# LOGIC.net
KiCad netlist of a schematic drawn in Altium Designer
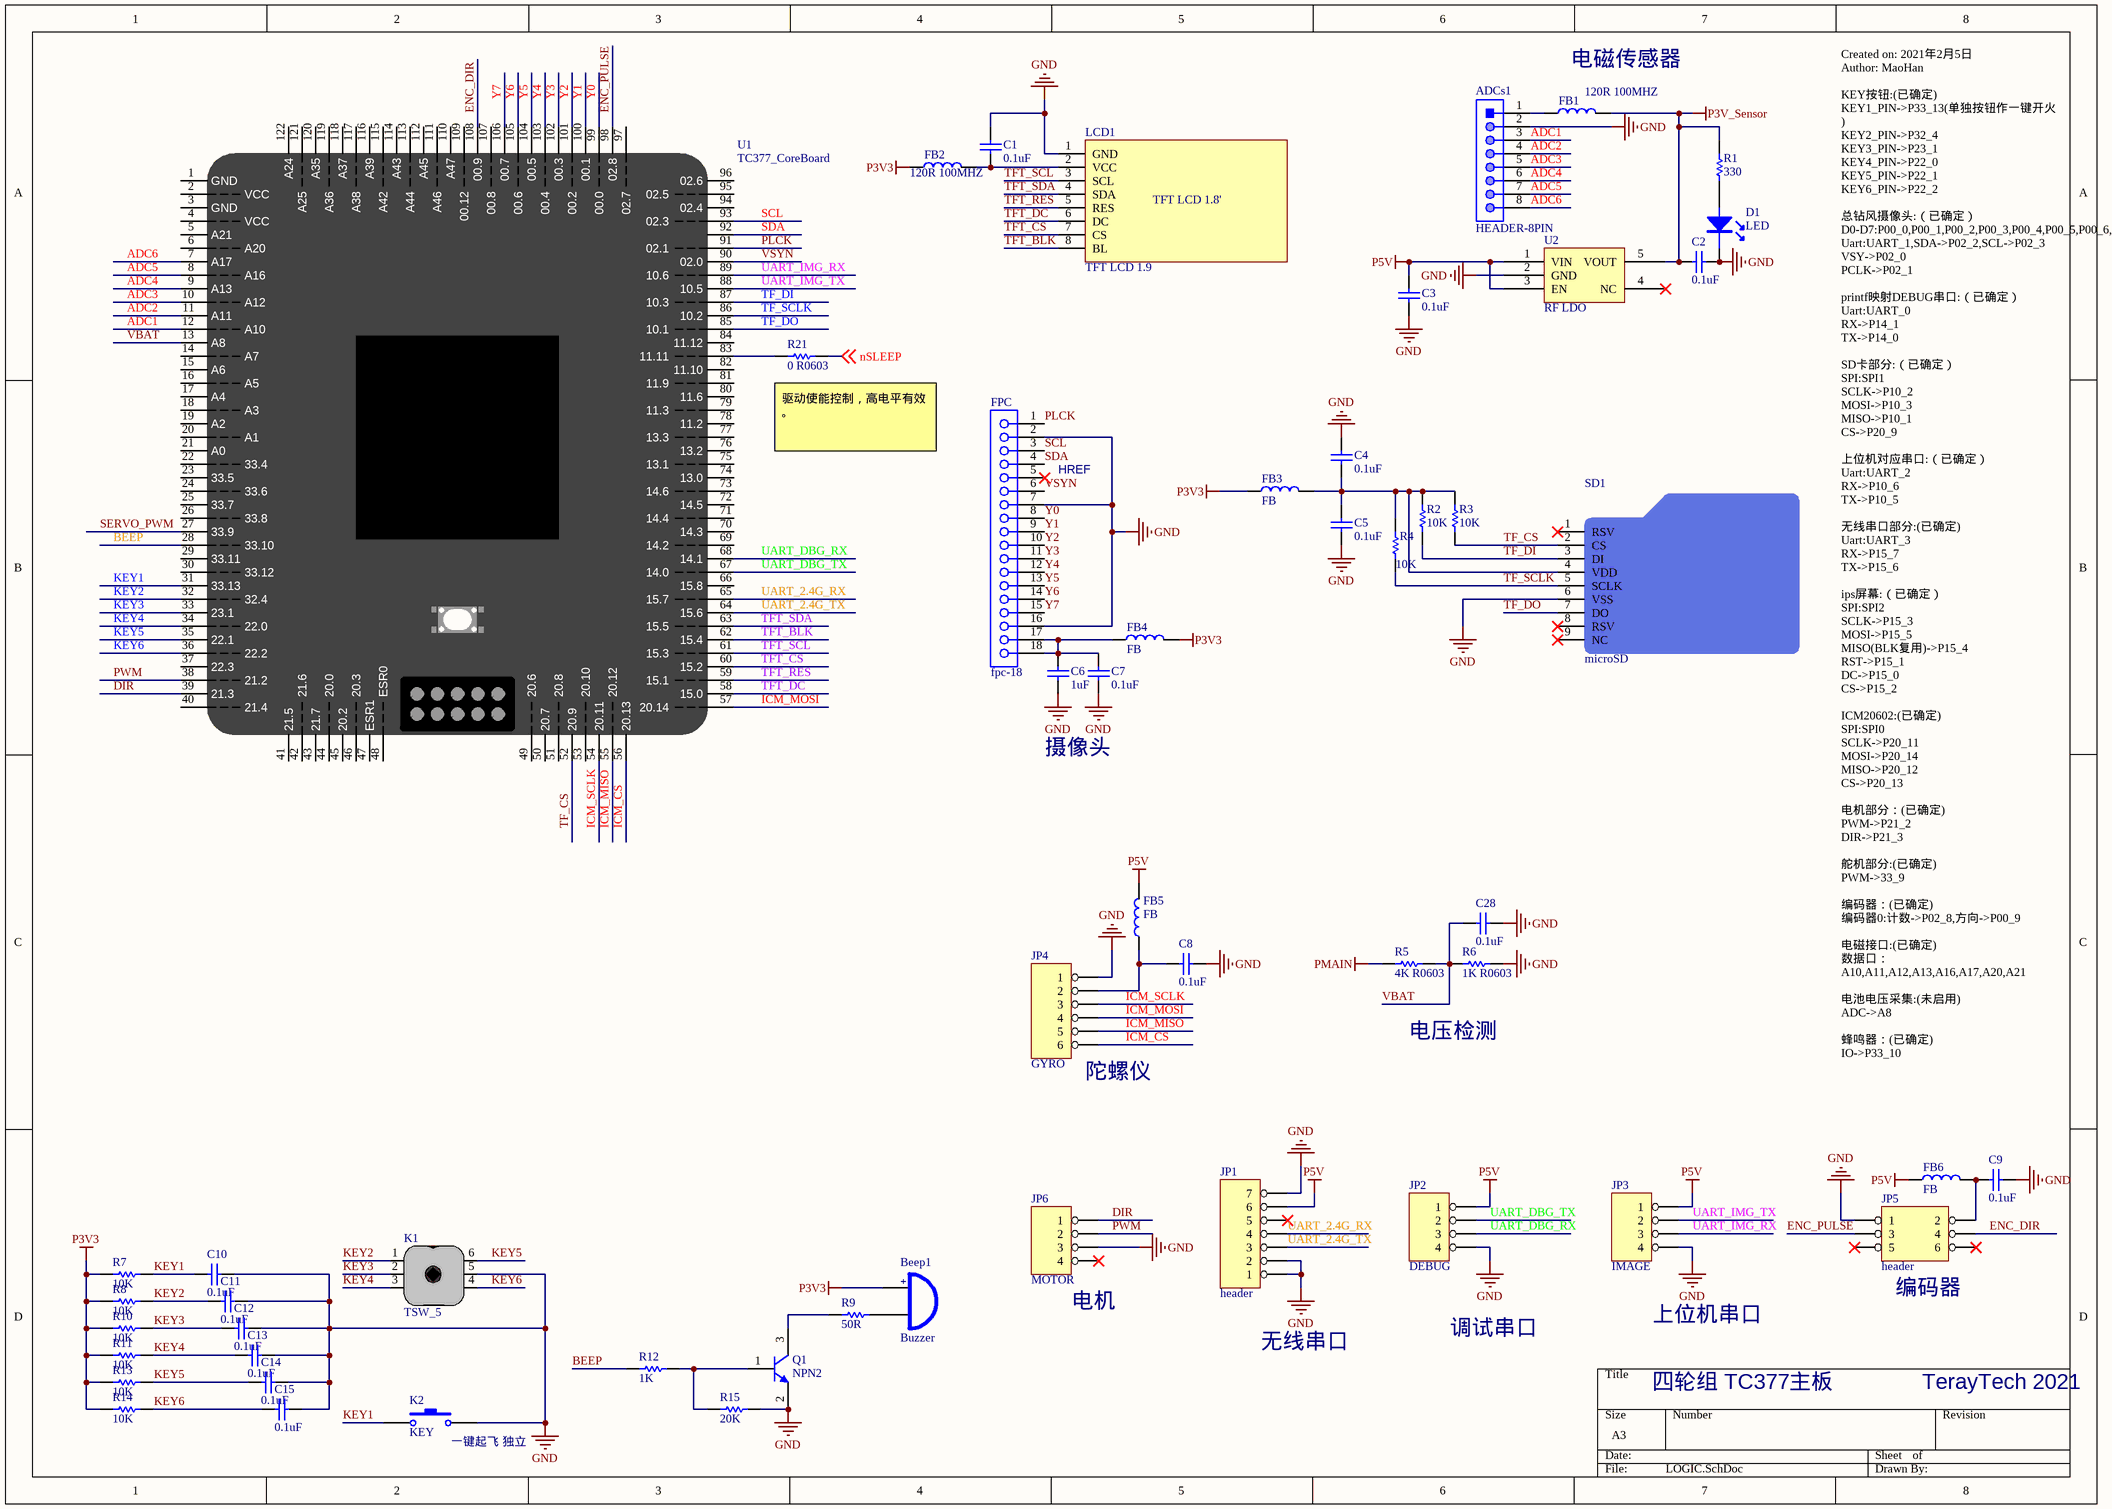
[diagram p0: LOGIC.SchDoc]

(export (version "E")
  (design (tool "Eeschema 10.0.6"))
  (components
    (comp (ref "ADCs1")
      (value "HEADER-8PIN")
      (footprint "HEADER_8P_1.25_RT")
      (libsource (lib "My Footprint") (part "HEADER-8PIN"))
    )
    (comp (ref "Beep1")
      (value "Buzzer")
      (footprint "BUZZER_9.6*9.6*5mm")
      (libsource (lib "My Footprint") (part "Buzzer"))
    )
    (comp (ref "C1")
      (value "0.1uF")
      (footprint "0603_C")
      (description "Capacitor")
      (fields (field (name "PUBLISHER") "Altium Limited"))
      (libsource (lib "My Footprint") (part "CAP"))
    )
    (comp (ref "C2")
      (value "0.1uF")
      (footprint "0603_C")
      (description "Capacitor")
      (fields (field (name "PUBLISHER") "Altium Limited"))
      (libsource (lib "My Footprint") (part "CAP"))
    )
    (comp (ref "C3")
      (value "0.1uF")
      (footprint "0603_C")
      (description "Capacitor")
      (fields (field (name "PUBLISHER") "Altium Limited"))
      (libsource (lib "My Footprint") (part "CAP"))
    )
    (comp (ref "C4")
      (value "0.1uF")
      (footprint "0603_C")
      (description "Capacitor")
      (fields (field (name "PUBLISHER") "Altium Limited"))
      (libsource (lib "My Footprint") (part "CAP"))
    )
    (comp (ref "C5")
      (value "0.1uF")
      (footprint "0603_C")
      (description "Capacitor")
      (fields (field (name "PUBLISHER") "Altium Limited"))
      (libsource (lib "My Footprint") (part "CAP"))
    )
    (comp (ref "C6")
      (value "1uF")
      (footprint "0603_C")
      (description "Capacitor")
      (fields (field (name "PUBLISHER") "Altium Limited"))
      (libsource (lib "") (part "CAP_1"))
    )
    (comp (ref "C7")
      (value "0.1uF")
      (footprint "0603_C")
      (description "Capacitor")
      (fields (field (name "PUBLISHER") "Altium Limited"))
      (libsource (lib "") (part "CAP_1"))
    )
    (comp (ref "C8")
      (value "0.1uF")
      (footprint "0603_C")
      (description "Capacitor")
      (fields (field (name "PUBLISHER") "Altium Limited"))
      (libsource (lib "My Footprint") (part "CAP"))
    )
    (comp (ref "C9")
      (value "0.1uF")
      (footprint "0603_C")
      (description "Capacitor")
      (fields (field (name "PUBLISHER") "Altium Limited"))
      (libsource (lib "My Footprint") (part "CAP"))
    )
    (comp (ref "C10")
      (value "0.1uF")
      (footprint "0603_C")
      (description "Capacitor")
      (fields (field (name "PUBLISHER") "Altium Limited"))
      (libsource (lib "My Footprint") (part "CAP"))
    )
    (comp (ref "C11")
      (value "0.1uF")
      (footprint "0603_C")
      (description "Capacitor")
      (fields (field (name "PUBLISHER") "Altium Limited"))
      (libsource (lib "My Footprint") (part "CAP"))
    )
    (comp (ref "C12")
      (value "0.1uF")
      (footprint "0603_C")
      (description "Capacitor")
      (fields (field (name "PUBLISHER") "Altium Limited"))
      (libsource (lib "My Footprint") (part "CAP"))
    )
    (comp (ref "C13")
      (value "0.1uF")
      (footprint "0603_C")
      (description "Capacitor")
      (fields (field (name "PUBLISHER") "Altium Limited"))
      (libsource (lib "My Footprint") (part "CAP"))
    )
    (comp (ref "C14")
      (value "0.1uF")
      (footprint "0603_C")
      (description "Capacitor")
      (fields (field (name "PUBLISHER") "Altium Limited"))
      (libsource (lib "My Footprint") (part "CAP"))
    )
    (comp (ref "C15")
      (value "0.1uF")
      (footprint "0603_C")
      (description "Capacitor")
      (fields (field (name "PUBLISHER") "Altium Limited"))
      (libsource (lib "My Footprint") (part "CAP"))
    )
    (comp (ref "C28")
      (value "0.1uF")
      (footprint "0603_C")
      (description "Capacitor")
      (fields (field (name "PUBLISHER") "Altium Limited"))
      (libsource (lib "My Footprint") (part "CAP"))
    )
    (comp (ref "D1")
      (value "LED")
      (footprint "0603_LED")
      (description "LED 发光二极管")
      (libsource (lib "My Footprint") (part "LED"))
    )
    (comp (ref "FB1")
      (value "120R 100MHZ")
      (footprint "FB0603")
      (description "120OHM@100MHZ 2A 25% 0603")
      (libsource (lib "My Footprint") (part "FB"))
    )
    (comp (ref "FB2")
      (value "120R 100MHZ")
      (footprint "FB0603")
      (description "120OHM@100MHZ 2A 25% 0603")
      (libsource (lib "My Footprint") (part "FB"))
    )
    (comp (ref "FB3")
      (value "FB")
      (footprint "FB0603")
      (description "磁珠")
      (libsource (lib "My Footprint") (part "FB"))
    )
    (comp (ref "FB4")
      (value "FB")
      (footprint "FB0603")
      (description "磁珠")
      (libsource (lib "My Footprint") (part "FB"))
    )
    (comp (ref "FB5")
      (value "FB")
      (footprint "FB0603")
      (description "磁珠")
      (libsource (lib "My Footprint") (part "FB"))
    )
    (comp (ref "FB6")
      (value "FB")
      (footprint "FB0603")
      (description "磁珠")
      (libsource (lib "My Footprint") (part "FB"))
    )
    (comp (ref "FPC")
      (value "fpc-18")
      (footprint "FPC_18_VER")
      (libsource (lib "My Footprint") (part "fpc-18"))
    )
    (comp (ref "JP1")
      (value "header")
      (footprint "header7")
      (libsource (lib "My Footprint") (part "HEADER 7"))
    )
    (comp (ref "JP2")
      (value "DEBUG")
      (footprint "header4")
      (libsource (lib "My Footprint") (part "HEADER 4"))
    )
    (comp (ref "JP3")
      (value "IMAGE")
      (footprint "header4")
      (libsource (lib "My Footprint") (part "HEADER 4"))
    )
    (comp (ref "JP4")
      (value "GYRO")
      (footprint "MX 1.25-WS-6P")
      (libsource (lib "My Footprint") (part "HEADER 6"))
    )
    (comp (ref "JP5")
      (value "header")
      (footprint "header2X3")
      (libsource (lib "My Footprint") (part "HEADER 3X2"))
    )
    (comp (ref "JP6")
      (value "MOTOR")
      (footprint "MX 1.25-WS-4P")
      (libsource (lib "My Footprint") (part "HEADER 4"))
    )
    (comp (ref "K1")
      (value "TSW_5")
      (footprint "TSW-10")
      (description "方向开关")
      (libsource (lib "My Footprint") (part "TSW_5"))
    )
    (comp (ref "K2")
      (value "KEY")
      (footprint "贴片复位开关")
      (description "Switch")
      (fields (field (name "PUBLISHER") "Altium Limited"))
      (libsource (lib "My Footprint") (part "KEY_2"))
    )
    (comp (ref "LCD1")
      (value "TFT LCD 1.9")
      (footprint "header8")
      (libsource (lib "My Footprint") (part "TFT LCD 1.9"))
    )
    (comp (ref "Q1")
      (value "NPN2")
      (footprint "SOT-23-3")
      (description "贴片")
      (libsource (lib "My Footprint") (part "NPN2"))
    )
    (comp (ref "R1")
      (value "330")
      (footprint "0603_R")
      (description "Resistor")
      (fields (field (name "PUBLISHER") "Altium Limited"))
      (libsource (lib "My Footprint") (part "RES0"))
    )
    (comp (ref "R2")
      (value "10K")
      (footprint "0603_R")
      (description "Resistor")
      (fields (field (name "PUBLISHER") "Altium Limited"))
      (libsource (lib "My Footprint") (part "RES"))
    )
    (comp (ref "R3")
      (value "10K")
      (footprint "0603_R")
      (description "Resistor")
      (fields (field (name "PUBLISHER") "Altium Limited"))
      (libsource (lib "My Footprint") (part "RES"))
    )
    (comp (ref "R4")
      (value "10K")
      (footprint "0603_R")
      (description "Resistor")
      (fields (field (name "PUBLISHER") "Altium Limited"))
      (libsource (lib "My Footprint") (part "RES"))
    )
    (comp (ref "R5")
      (value "4K R0603")
      (footprint "0603_R")
      (description "Resistor")
      (fields (field (name "PUBLISHER") "Altium Limited"))
      (libsource (lib "My Footprint") (part "RES"))
    )
    (comp (ref "R6")
      (value "1K R0603")
      (footprint "0603_R")
      (description "Resistor")
      (fields (field (name "PUBLISHER") "Altium Limited"))
      (libsource (lib "My Footprint") (part "RES"))
    )
    (comp (ref "R7")
      (value "10K")
      (footprint "0603_R")
      (description "Resistor")
      (fields (field (name "PUBLISHER") "Altium Limited"))
      (libsource (lib "My Footprint") (part "RES0"))
    )
    (comp (ref "R8")
      (value "10K")
      (footprint "0603_R")
      (description "Resistor")
      (fields (field (name "PUBLISHER") "Altium Limited"))
      (libsource (lib "My Footprint") (part "RES0"))
    )
    (comp (ref "R9")
      (value "50R")
      (footprint "0603_R")
      (description "Resistor")
      (fields (field (name "PUBLISHER") "Altium Limited"))
      (libsource (lib "My Footprint") (part "RES"))
    )
    (comp (ref "R10")
      (value "10K")
      (footprint "0603_R")
      (description "Resistor")
      (fields (field (name "PUBLISHER") "Altium Limited"))
      (libsource (lib "My Footprint") (part "RES0"))
    )
    (comp (ref "R11")
      (value "10K")
      (footprint "0603_R")
      (description "Resistor")
      (fields (field (name "PUBLISHER") "Altium Limited"))
      (libsource (lib "My Footprint") (part "RES0"))
    )
    (comp (ref "R12")
      (value "1K")
      (footprint "0603_R")
      (description "Resistor")
      (fields (field (name "PUBLISHER") "Altium Limited"))
      (libsource (lib "") (part "RES_1"))
    )
    (comp (ref "R13")
      (value "10K")
      (footprint "0603_R")
      (description "Resistor")
      (fields (field (name "PUBLISHER") "Altium Limited"))
      (libsource (lib "My Footprint") (part "RES0"))
    )
    (comp (ref "R14")
      (value "10K")
      (footprint "0603_R")
      (description "Resistor")
      (fields (field (name "PUBLISHER") "Altium Limited"))
      (libsource (lib "My Footprint") (part "RES0"))
    )
    (comp (ref "R15")
      (value "20K")
      (footprint "0603_R")
      (description "Resistor")
      (fields (field (name "PUBLISHER") "Altium Limited"))
      (libsource (lib "") (part "RES_1"))
    )
    (comp (ref "R21")
      (value "0 R0603")
      (footprint "0603_R")
      (description "Resistor")
      (fields (field (name "PUBLISHER") "Altium Limited"))
      (libsource (lib "My Footprint") (part "RES"))
    )
    (comp (ref "SD1")
      (value "microSD")
      (footprint "microSD_CARD")
      (libsource (lib "My Footprint") (part "microSD_1"))
    )
    (comp (ref "U1")
      (value "TC377_CoreBoard")
      (footprint "TC377_CoreBoard")
      (description "逐飞科技TC377核心板")
      (libsource (lib "TC377_CoreBoard") (part "TC377_CoreBoard"))
    )
    (comp (ref "U2") (value "RF LDO") (footprint "SOT-23-5") (libsource (lib "My Footprint") (part "ADP150")))
  )
  (nets
    (net (code "1") (name "/ADC1") (class "Default")
      (node (ref "ADCs1") (pin "3") (pinfunction "3_3") (pintype "passive"))
      (node (ref "U1") (pin "12") (pinfunction "A10_12") (pintype "passive"))
    )
    (net (code "2") (name "/ADC2") (class "Default")
      (node (ref "ADCs1") (pin "4") (pinfunction "4_4") (pintype "passive"))
      (node (ref "U1") (pin "11") (pinfunction "A11_11") (pintype "passive"))
    )
    (net (code "3") (name "/ADC3") (class "Default")
      (node (ref "ADCs1") (pin "5") (pinfunction "5_5") (pintype "passive"))
      (node (ref "U1") (pin "10") (pinfunction "A12_10") (pintype "passive"))
    )
    (net (code "4") (name "/ADC4") (class "Default")
      (node (ref "ADCs1") (pin "6") (pinfunction "6_6") (pintype "passive"))
      (node (ref "U1") (pin "9") (pinfunction "A13_9") (pintype "passive"))
    )
    (net (code "5") (name "/ADC5") (class "Default")
      (node (ref "ADCs1") (pin "7") (pinfunction "7_7") (pintype "passive"))
      (node (ref "U1") (pin "8") (pinfunction "A16_8") (pintype "passive"))
    )
    (net (code "6") (name "/ADC6") (class "Default")
      (node (ref "ADCs1") (pin "8") (pinfunction "8_8") (pintype "passive"))
      (node (ref "U1") (pin "7") (pinfunction "A17_7") (pintype "passive"))
    )
    (net (code "7") (name "/BEEP") (class "Default")
      (node (ref "R12") (pin "1") (pinfunction "1_1") (pintype "passive"))
      (node (ref "U1") (pin "28") (pinfunction "33.10_28") (pintype "passive"))
    )
    (net (code "8") (name "/DIR") (class "Default")
      (node (ref "JP6") (pin "1") (pinfunction "1_1") (pintype "passive"))
      (node (ref "U1") (pin "39") (pinfunction "21.3_39") (pintype "passive"))
    )
    (net (code "9") (name "/ENC_DIR") (class "Default")
      (node (ref "JP5") (pin "4") (pinfunction "4_4") (pintype "passive"))
      (node (ref "U1") (pin "108") (pinfunction "00.9_108") (pintype "passive"))
    )
    (net (code "10") (name "/ENC_PULSE") (class "Default")
      (node (ref "JP5") (pin "3") (pinfunction "3_3") (pintype "passive"))
      (node (ref "U1") (pin "98") (pinfunction "02.8_98") (pintype "passive"))
    )
    (net (code "11") (name "/ICM_CS") (class "Default")
      (node (ref "JP4") (pin "6") (pinfunction "6_6") (pintype "passive"))
      (node (ref "U1") (pin "56") (pinfunction "20.13_56") (pintype "passive"))
    )
    (net (code "12") (name "/ICM_MISO") (class "Default")
      (node (ref "JP4") (pin "5") (pinfunction "5_5") (pintype "passive"))
      (node (ref "U1") (pin "55") (pinfunction "20.12_55") (pintype "passive"))
    )
    (net (code "13") (name "/ICM_MOSI") (class "Default")
      (node (ref "JP4") (pin "4") (pinfunction "4_4") (pintype "passive"))
      (node (ref "U1") (pin "57") (pinfunction "20.14_57") (pintype "passive"))
    )
    (net (code "14") (name "/ICM_SCLK") (class "Default")
      (node (ref "JP4") (pin "3") (pinfunction "3_3") (pintype "passive"))
      (node (ref "U1") (pin "54") (pinfunction "20.11_54") (pintype "passive"))
    )
    (net (code "15") (name "/KEY1") (class "Default")
      (node (ref "C10") (pin "1") (pinfunction "1_1") (pintype "passive"))
      (node (ref "K2") (pin "1") (pinfunction "1_1") (pintype "passive"))
      (node (ref "R7") (pin "2") (pinfunction "2_2") (pintype "passive"))
      (node (ref "U1") (pin "31") (pinfunction "33.13_31") (pintype "passive"))
    )
    (net (code "16") (name "/KEY2") (class "Default")
      (node (ref "C11") (pin "1") (pinfunction "1_1") (pintype "passive"))
      (node (ref "K1") (pin "1") (pintype "passive"))
      (node (ref "R8") (pin "2") (pinfunction "2_2") (pintype "passive"))
      (node (ref "U1") (pin "32") (pinfunction "32.4_32") (pintype "passive"))
    )
    (net (code "17") (name "/KEY3") (class "Default")
      (node (ref "C12") (pin "1") (pinfunction "1_1") (pintype "passive"))
      (node (ref "K1") (pin "2") (pintype "passive"))
      (node (ref "R10") (pin "2") (pinfunction "2_2") (pintype "passive"))
      (node (ref "U1") (pin "33") (pinfunction "23.1_33") (pintype "passive"))
    )
    (net (code "18") (name "/KEY4") (class "Default")
      (node (ref "C13") (pin "1") (pinfunction "1_1") (pintype "passive"))
      (node (ref "K1") (pin "3") (pintype "passive"))
      (node (ref "R11") (pin "2") (pinfunction "2_2") (pintype "passive"))
      (node (ref "U1") (pin "34") (pinfunction "22.0_34") (pintype "passive"))
    )
    (net (code "19") (name "/KEY5") (class "Default")
      (node (ref "C14") (pin "1") (pinfunction "1_1") (pintype "passive"))
      (node (ref "K1") (pin "6") (pintype "passive"))
      (node (ref "R13") (pin "2") (pinfunction "2_2") (pintype "passive"))
      (node (ref "U1") (pin "35") (pinfunction "22.1_35") (pintype "passive"))
    )
    (net (code "20") (name "/KEY6") (class "Default")
      (node (ref "C15") (pin "1") (pinfunction "1_1") (pintype "passive"))
      (node (ref "K1") (pin "4") (pintype "passive"))
      (node (ref "R14") (pin "2") (pinfunction "2_2") (pintype "passive"))
      (node (ref "U1") (pin "36") (pinfunction "22.2_36") (pintype "passive"))
    )
    (net (code "21") (name "/PLCK") (class "Default")
      (node (ref "FPC") (pin "1") (pinfunction "1_1") (pintype "passive"))
      (node (ref "U1") (pin "91") (pinfunction "02.1_91") (pintype "passive"))
    )
    (net (code "22") (name "/PWM") (class "Default")
      (node (ref "JP6") (pin "2") (pinfunction "2_2") (pintype "passive"))
      (node (ref "U1") (pin "38") (pinfunction "21.2_38") (pintype "passive"))
    )
    (net (code "23") (name "/SCL") (class "Default")
      (node (ref "FPC") (pin "3") (pinfunction "3_3") (pintype "passive"))
      (node (ref "U1") (pin "93") (pinfunction "02.3_93") (pintype "passive"))
    )
    (net (code "24") (name "/SDA") (class "Default")
      (node (ref "FPC") (pin "4") (pinfunction "4_4") (pintype "passive"))
      (node (ref "U1") (pin "92") (pintype "passive"))
    )
    (net (code "25") (name "/SERVO_PWM") (class "Default")
      (node (ref "U1") (pin "27") (pinfunction "33.9_27") (pintype "passive"))
    )
    (net (code "26") (name "/TFT_BLK") (class "Default")
      (node (ref "LCD1") (pin "8") (pinfunction "BL_8") (pintype "passive"))
      (node (ref "U1") (pin "62") (pinfunction "15.4_62") (pintype "passive"))
    )
    (net (code "27") (name "/TFT_CS") (class "Default")
      (node (ref "LCD1") (pin "7") (pinfunction "CS_7") (pintype "passive"))
      (node (ref "U1") (pin "60") (pinfunction "15.2_60") (pintype "passive"))
    )
    (net (code "28") (name "/TFT_DC") (class "Default")
      (node (ref "LCD1") (pin "6") (pinfunction "DC_6") (pintype "passive"))
      (node (ref "U1") (pin "58") (pinfunction "15.0_58") (pintype "passive"))
    )
    (net (code "29") (name "/TFT_RES") (class "Default")
      (node (ref "LCD1") (pin "5") (pinfunction "RES_5") (pintype "passive"))
      (node (ref "U1") (pin "59") (pinfunction "15.1_59") (pintype "passive"))
    )
    (net (code "30") (name "/TFT_SCL") (class "Default")
      (node (ref "LCD1") (pin "3") (pinfunction "SCL_3") (pintype "passive"))
      (node (ref "U1") (pin "61") (pinfunction "15.3_61") (pintype "passive"))
    )
    (net (code "31") (name "/TFT_SDA") (class "Default")
      (node (ref "LCD1") (pin "4") (pinfunction "SDA_4") (pintype "passive"))
      (node (ref "U1") (pin "63") (pinfunction "15.5_63") (pintype "passive"))
    )
    (net (code "32") (name "/TF_CS") (class "Default")
      (node (ref "R3") (pin "1") (pinfunction "1_1") (pintype "passive"))
      (node (ref "SD1") (pin "2") (pinfunction "CS_2") (pintype "passive"))
      (node (ref "U1") (pin "52") (pinfunction "20.9_52") (pintype "passive"))
    )
    (net (code "33") (name "/TF_DI") (class "Default")
      (node (ref "R2") (pin "1") (pinfunction "1_1") (pintype "passive"))
      (node (ref "SD1") (pin "3") (pinfunction "DI_3") (pintype "passive"))
      (node (ref "U1") (pin "87") (pinfunction "10.3_87") (pintype "passive"))
    )
    (net (code "34") (name "/TF_DO") (class "Default")
      (node (ref "SD1") (pin "7") (pinfunction "DO_7") (pintype "passive"))
      (node (ref "U1") (pin "85") (pinfunction "10.1_85") (pintype "passive"))
    )
    (net (code "35") (name "/TF_SCLK") (class "Default")
      (node (ref "R4") (pin "1") (pinfunction "1_1") (pintype "passive"))
      (node (ref "SD1") (pin "5") (pinfunction "SCLK_5") (pintype "passive"))
      (node (ref "U1") (pin "86") (pinfunction "10.2_86") (pintype "passive"))
    )
    (net (code "36") (name "/UART_2.4G_RX") (class "Default")
      (node (ref "JP1") (pin "4") (pinfunction "4_4") (pintype "passive"))
      (node (ref "U1") (pin "65") (pinfunction "15.7_65") (pintype "passive"))
    )
    (net (code "37") (name "/UART_2.4G_TX") (class "Default")
      (node (ref "JP1") (pin "3") (pinfunction "3_3") (pintype "passive"))
      (node (ref "U1") (pin "64") (pinfunction "15.6_64") (pintype "passive"))
    )
    (net (code "38") (name "/UART_DBG_RX") (class "Default")
      (node (ref "JP2") (pin "3") (pinfunction "3_3") (pintype "passive"))
      (node (ref "U1") (pin "68") (pinfunction "14.1_68") (pintype "passive"))
    )
    (net (code "39") (name "/UART_DBG_TX") (class "Default")
      (node (ref "JP2") (pin "2") (pinfunction "2_2") (pintype "passive"))
      (node (ref "U1") (pin "67") (pinfunction "14.0_67") (pintype "passive"))
    )
    (net (code "40") (name "/UART_IMG_RX") (class "Default")
      (node (ref "JP3") (pin "3") (pinfunction "3_3") (pintype "passive"))
      (node (ref "U1") (pin "89") (pinfunction "10.6_89") (pintype "passive"))
    )
    (net (code "41") (name "/UART_IMG_TX") (class "Default")
      (node (ref "JP3") (pin "2") (pinfunction "2_2") (pintype "passive"))
      (node (ref "U1") (pin "88") (pinfunction "10.5_88") (pintype "passive"))
    )
    (net (code "42") (name "/VBAT") (class "Default")
      (node (ref "C28") (pin "2") (pinfunction "2_2") (pintype "passive"))
      (node (ref "R5") (pin "2") (pinfunction "2_2") (pintype "passive"))
      (node (ref "R6") (pin "1") (pinfunction "1_1") (pintype "passive"))
      (node (ref "U1") (pin "13") (pinfunction "A8_13") (pintype "passive"))
    )
    (net (code "43") (name "/VSYN") (class "Default")
      (node (ref "FPC") (pin "6") (pinfunction "6_6") (pintype "passive"))
      (node (ref "U1") (pin "90") (pinfunction "02.0_90") (pintype "passive"))
    )
    (net (code "44") (name "/Y0") (class "Default")
      (node (ref "FPC") (pin "8") (pinfunction "8_8") (pintype "passive"))
      (node (ref "U1") (pin "99") (pinfunction "00.0_99") (pintype "passive"))
    )
    (net (code "45") (name "/Y1") (class "Default")
      (node (ref "FPC") (pin "9") (pinfunction "9_9") (pintype "passive"))
      (node (ref "U1") (pin "100") (pinfunction "00.1_100") (pintype "passive"))
    )
    (net (code "46") (name "/Y2") (class "Default")
      (node (ref "FPC") (pin "10") (pinfunction "10_10") (pintype "passive"))
      (node (ref "U1") (pin "101") (pinfunction "00.2_101") (pintype "passive"))
    )
    (net (code "47") (name "/Y3") (class "Default")
      (node (ref "FPC") (pin "11") (pinfunction "11_11") (pintype "passive"))
      (node (ref "U1") (pin "102") (pinfunction "00.3_102") (pintype "passive"))
    )
    (net (code "48") (name "/Y4") (class "Default")
      (node (ref "FPC") (pin "12") (pinfunction "12_12") (pintype "passive"))
      (node (ref "U1") (pin "103") (pinfunction "00.4_103") (pintype "passive"))
    )
    (net (code "49") (name "/Y5") (class "Default")
      (node (ref "FPC") (pin "13") (pinfunction "13_13") (pintype "passive"))
      (node (ref "U1") (pin "104") (pinfunction "00.5_104") (pintype "passive"))
    )
    (net (code "50") (name "/Y6") (class "Default")
      (node (ref "FPC") (pin "14") (pinfunction "14_14") (pintype "passive"))
      (node (ref "U1") (pin "105") (pinfunction "00.6_105") (pintype "passive"))
    )
    (net (code "51") (name "/Y7") (class "Default")
      (node (ref "FPC") (pin "15") (pinfunction "15_15") (pintype "passive"))
      (node (ref "U1") (pin "106") (pinfunction "00.7_106") (pintype "passive"))
    )
    (net (code "52") (name "GND") (class "Default")
      (node (ref "ADCs1") (pin "2") (pinfunction "2_2") (pintype "passive"))
      (node (ref "C1") (pin "2") (pinfunction "2_2") (pintype "passive"))
      (node (ref "C10") (pin "2") (pinfunction "2_2") (pintype "passive"))
      (node (ref "C11") (pin "2") (pinfunction "2_2") (pintype "passive"))
      (node (ref "C12") (pin "2") (pinfunction "2_2") (pintype "passive"))
      (node (ref "C13") (pin "2") (pinfunction "2_2") (pintype "passive"))
      (node (ref "C14") (pin "2") (pinfunction "2_2") (pintype "passive"))
      (node (ref "C15") (pin "2") (pinfunction "2_2") (pintype "passive"))
      (node (ref "C2") (pin "1") (pinfunction "1_1") (pintype "passive"))
      (node (ref "C28") (pin "1") (pinfunction "1_1") (pintype "passive"))
      (node (ref "C3") (pin "2") (pinfunction "2_2") (pintype "passive"))
      (node (ref "C4") (pin "1") (pinfunction "1_1") (pintype "passive"))
      (node (ref "C5") (pin "1") (pinfunction "1_1") (pintype "passive"))
      (node (ref "C6") (pin "2") (pinfunction "2_2") (pintype "passive"))
      (node (ref "C7") (pin "2") (pinfunction "2_2") (pintype "passive"))
      (node (ref "C8") (pin "1") (pinfunction "1_1") (pintype "passive"))
      (node (ref "C9") (pin "2") (pinfunction "2_2") (pintype "passive"))
      (node (ref "D1") (pin "2") (pinfunction "K_2") (pintype "passive"))
      (node (ref "FPC") (pin "16") (pinfunction "16_16") (pintype "passive"))
      (node (ref "FPC") (pin "2") (pinfunction "2_2") (pintype "passive"))
      (node (ref "FPC") (pin "7") (pinfunction "7_7") (pintype "passive"))
      (node (ref "JP1") (pin "1") (pinfunction "1_1") (pintype "passive"))
      (node (ref "JP1") (pin "2") (pinfunction "2_2") (pintype "passive"))
      (node (ref "JP1") (pin "7") (pinfunction "7_7") (pintype "passive"))
      (node (ref "JP2") (pin "4") (pinfunction "4_4") (pintype "passive"))
      (node (ref "JP3") (pin "4") (pinfunction "4_4") (pintype "passive"))
      (node (ref "JP4") (pin "1") (pinfunction "1_1") (pintype "passive"))
      (node (ref "JP5") (pin "1") (pinfunction "1_1") (pintype "passive"))
      (node (ref "JP6") (pin "3") (pinfunction "3_3") (pintype "passive"))
      (node (ref "K1") (pin "5") (pintype "passive"))
      (node (ref "K2") (pin "2") (pinfunction "2_2") (pintype "passive"))
      (node (ref "LCD1") (pin "1") (pinfunction "GND_1") (pintype "passive"))
      (node (ref "Q1") (pin "2") (pinfunction "E_2") (pintype "passive"))
      (node (ref "R15") (pin "2") (pinfunction "2_2") (pintype "passive"))
      (node (ref "R6") (pin "2") (pinfunction "2_2") (pintype "passive"))
      (node (ref "SD1") (pin "6") (pinfunction "VSS_6") (pintype "passive"))
      (node (ref "U2") (pin "2") (pinfunction "GND_2") (pintype "passive"))
    )
    (net (code "53") (name "Net-(ADCs1-Pad1)") (class "Default")
      (node (ref "ADCs1") (pin "1") (pinfunction "1_1") (pintype "passive"))
      (node (ref "FB1") (pin "1") (pinfunction "1_1") (pintype "passive"))
    )
    (net (code "54") (name "Net-(Beep1-B)") (class "Default")
      (node (ref "Beep1") (pin "2") (pinfunction "B_2") (pintype "passive"))
      (node (ref "R9") (pin "2") (pinfunction "2_2") (pintype "passive"))
    )
    (net (code "55") (name "Net-(C6-Pad1)") (class "Default")
      (node (ref "C6") (pin "1") (pinfunction "1_1") (pintype "passive"))
      (node (ref "C7") (pin "1") (pinfunction "1_1") (pintype "passive"))
      (node (ref "FB4") (pin "1") (pinfunction "1_1") (pintype "passive"))
      (node (ref "FPC") (pin "17") (pinfunction "17_17") (pintype "passive"))
      (node (ref "FPC") (pin "18") (pinfunction "18_18") (pintype "passive"))
    )
    (net (code "56") (name "Net-(C8-Pad2)") (class "Default")
      (node (ref "C8") (pin "2") (pinfunction "2_2") (pintype "passive"))
      (node (ref "FB5") (pin "1") (pinfunction "1_1") (pintype "passive"))
      (node (ref "JP4") (pin "2") (pinfunction "2_2") (pintype "passive"))
    )
    (net (code "57") (name "Net-(C9-Pad1)") (class "Default")
      (node (ref "C9") (pin "1") (pinfunction "1_1") (pintype "passive"))
      (node (ref "FB6") (pin "2") (pinfunction "2_2") (pintype "passive"))
      (node (ref "JP5") (pin "2") (pinfunction "2_2") (pintype "passive"))
    )
    (net (code "58") (name "Net-(D1-A)") (class "Default")
      (node (ref "D1") (pin "1") (pinfunction "A_1") (pintype "passive"))
      (node (ref "R1") (pin "1") (pinfunction "1_1") (pintype "passive"))
    )
    (net (code "59") (name "Net-(LCD1-VCC)") (class "Default")
      (node (ref "C1") (pin "1") (pinfunction "1_1") (pintype "passive"))
      (node (ref "FB2") (pin "2") (pinfunction "2_2") (pintype "passive"))
      (node (ref "LCD1") (pin "2") (pinfunction "VCC_2") (pintype "passive"))
    )
    (net (code "60") (name "Net-(Q1-B)") (class "Default")
      (node (ref "Q1") (pin "1") (pinfunction "B_1") (pintype "passive"))
      (node (ref "R12") (pin "2") (pinfunction "2_2") (pintype "passive"))
      (node (ref "R15") (pin "1") (pinfunction "1_1") (pintype "passive"))
    )
    (net (code "61") (name "Net-(Q1-C)") (class "Default")
      (node (ref "Q1") (pin "3") (pinfunction "C_3") (pintype "passive"))
      (node (ref "R9") (pin "1") (pinfunction "1_1") (pintype "passive"))
    )
    (net (code "62") (name "Net-(SD1-VDD)") (class "Default")
      (node (ref "C4") (pin "2") (pinfunction "2_2") (pintype "passive"))
      (node (ref "C5") (pin "2") (pinfunction "2_2") (pintype "passive"))
      (node (ref "FB3") (pin "2") (pinfunction "2_2") (pintype "passive"))
      (node (ref "R2") (pin "2") (pinfunction "2_2") (pintype "passive"))
      (node (ref "R3") (pin "2") (pinfunction "2_2") (pintype "passive"))
      (node (ref "R4") (pin "2") (pinfunction "2_2") (pintype "passive"))
      (node (ref "SD1") (pin "4") (pinfunction "VDD_4") (pintype "passive"))
    )
    (net (code "63") (name "Net-(U1-11.11)") (class "Default")
      (node (ref "R21") (pin "1") (pinfunction "1_1") (pintype "passive"))
      (node (ref "U1") (pin "83") (pinfunction "11.11_83") (pintype "passive"))
    )
    (net (code "64") (name "P3V3") (class "Default")
      (node (ref "Beep1") (pin "1") (pinfunction "A_1") (pintype "passive"))
      (node (ref "FB2") (pin "1") (pinfunction "1_1") (pintype "passive"))
      (node (ref "FB3") (pin "1") (pinfunction "1_1") (pintype "passive"))
      (node (ref "FB4") (pin "2") (pinfunction "2_2") (pintype "passive"))
      (node (ref "R10") (pin "1") (pinfunction "1_1") (pintype "passive"))
      (node (ref "R11") (pin "1") (pinfunction "1_1") (pintype "passive"))
      (node (ref "R13") (pin "1") (pinfunction "1_1") (pintype "passive"))
      (node (ref "R14") (pin "1") (pinfunction "1_1") (pintype "passive"))
      (node (ref "R7") (pin "1") (pinfunction "1_1") (pintype "passive"))
      (node (ref "R8") (pin "1") (pinfunction "1_1") (pintype "passive"))
    )
    (net (code "65") (name "P3V_Sensor") (class "Default")
      (node (ref "C2") (pin "2") (pinfunction "2_2") (pintype "passive"))
      (node (ref "FB1") (pin "2") (pinfunction "2_2") (pintype "passive"))
      (node (ref "R1") (pin "2") (pinfunction "2_2") (pintype "passive"))
      (node (ref "U2") (pin "5") (pinfunction "VOUT_5") (pintype "passive"))
    )
    (net (code "66") (name "P5V") (class "Default")
      (node (ref "C3") (pin "1") (pinfunction "1_1") (pintype "passive"))
      (node (ref "FB5") (pin "2") (pinfunction "2_2") (pintype "passive"))
      (node (ref "FB6") (pin "1") (pinfunction "1_1") (pintype "passive"))
      (node (ref "JP1") (pin "6") (pinfunction "6_6") (pintype "passive"))
      (node (ref "JP2") (pin "1") (pinfunction "1_1") (pintype "passive"))
      (node (ref "JP3") (pin "1") (pinfunction "1_1") (pintype "passive"))
      (node (ref "U2") (pin "1") (pinfunction "VIN_1") (pintype "passive"))
      (node (ref "U2") (pin "3") (pinfunction "EN_3") (pintype "passive"))
    )
    (net (code "67") (name "PMAIN") (class "Default")
      (node (ref "R5") (pin "1") (pinfunction "1_1") (pintype "passive"))
    )
    (net (code "68") (name "nSLEEP") (class "Default")
      (node (ref "R21") (pin "2") (pinfunction "2_2") (pintype "passive"))
    )
    (net (code "69") (name "unconnected-(FPC-Pad5)") (class "Default")
      (node (ref "FPC") (pin "5") (pinfunction "5_5") (pintype "passive+no_connect"))
    )
    (net (code "70") (name "unconnected-(JP1-Pad5)") (class "Default")
      (node (ref "JP1") (pin "5") (pinfunction "5_5") (pintype "passive+no_connect"))
    )
    (net (code "71") (name "unconnected-(JP5-Pad5)") (class "Default")
      (node (ref "JP5") (pin "5") (pinfunction "5_5") (pintype "passive+no_connect"))
    )
    (net (code "72") (name "unconnected-(JP5-Pad6)") (class "Default")
      (node (ref "JP5") (pin "6") (pinfunction "6_6") (pintype "passive+no_connect"))
    )
    (net (code "73") (name "unconnected-(JP6-Pad4)") (class "Default")
      (node (ref "JP6") (pin "4") (pinfunction "4_4") (pintype "passive+no_connect"))
    )
    (net (code "74") (name "unconnected-(SD1-NC-Pad9)") (class "Default")
      (node (ref "SD1") (pin "9") (pinfunction "NC_9") (pintype "passive+no_connect"))
    )
    (net (code "75") (name "unconnected-(SD1-RSV-Pad1)") (class "Default")
      (node (ref "SD1") (pin "1") (pinfunction "RSV_1") (pintype "passive+no_connect"))
    )
    (net (code "76") (name "unconnected-(SD1-RSV-Pad8)") (class "Default")
      (node (ref "SD1") (pin "8") (pinfunction "RSV_8") (pintype "passive+no_connect"))
    )
    (net (code "77") (name "unconnected-(U1-00.8-Pad107)") (class "Default")
      (node (ref "U1") (pin "107") (pinfunction "00.8_107") (pintype "passive"))
    )
    (net (code "78") (name "unconnected-(U1-00.12-Pad109)") (class "Default")
      (node (ref "U1") (pin "109") (pinfunction "00.12_109") (pintype "passive"))
    )
    (net (code "79") (name "unconnected-(U1-02.4-Pad94)") (class "Default")
      (node (ref "U1") (pin "94") (pinfunction "02.4_94") (pintype "passive"))
    )
    (net (code "80") (name "unconnected-(U1-02.5-Pad95)") (class "Default")
      (node (ref "U1") (pin "95") (pinfunction "02.5_95") (pintype "passive"))
    )
    (net (code "81") (name "unconnected-(U1-02.6-Pad96)") (class "Default")
      (node (ref "U1") (pin "96") (pinfunction "02.6_96") (pintype "passive"))
    )
    (net (code "82") (name "unconnected-(U1-02.7-Pad97)") (class "Default")
      (node (ref "U1") (pin "97") (pinfunction "02.7_97") (pintype "passive"))
    )
    (net (code "83") (name "unconnected-(U1-11.2-Pad78)") (class "Default")
      (node (ref "U1") (pin "78") (pinfunction "11.2_78") (pintype "passive"))
    )
    (net (code "84") (name "unconnected-(U1-11.3-Pad79)") (class "Default")
      (node (ref "U1") (pin "79") (pinfunction "11.3_79") (pintype "passive"))
    )
    (net (code "85") (name "unconnected-(U1-11.6-Pad80)") (class "Default")
      (node (ref "U1") (pin "80") (pinfunction "11.6_80") (pintype "passive"))
    )
    (net (code "86") (name "unconnected-(U1-11.9-Pad81)") (class "Default")
      (node (ref "U1") (pin "81") (pinfunction "11.9_81") (pintype "passive"))
    )
    (net (code "87") (name "unconnected-(U1-11.10-Pad82)") (class "Default")
      (node (ref "U1") (pin "82") (pinfunction "11.10_82") (pintype "passive"))
    )
    (net (code "88") (name "unconnected-(U1-11.12-Pad84)") (class "Default")
      (node (ref "U1") (pin "84") (pinfunction "11.12_84") (pintype "passive"))
    )
    (net (code "89") (name "unconnected-(U1-13.0-Pad74)") (class "Default")
      (node (ref "U1") (pin "74") (pinfunction "13.0_74") (pintype "passive"))
    )
    (net (code "90") (name "unconnected-(U1-13.1-Pad75)") (class "Default")
      (node (ref "U1") (pin "75") (pinfunction "13.1_75") (pintype "passive"))
    )
    (net (code "91") (name "unconnected-(U1-13.2-Pad76)") (class "Default")
      (node (ref "U1") (pin "76") (pinfunction "13.2_76") (pintype "passive"))
    )
    (net (code "92") (name "unconnected-(U1-13.3-Pad77)") (class "Default")
      (node (ref "U1") (pin "77") (pinfunction "13.3_77") (pintype "passive"))
    )
    (net (code "93") (name "unconnected-(U1-14.2-Pad69)") (class "Default")
      (node (ref "U1") (pin "69") (pinfunction "14.2_69") (pintype "passive"))
    )
    (net (code "94") (name "unconnected-(U1-14.3-Pad70)") (class "Default")
      (node (ref "U1") (pin "70") (pinfunction "14.3_70") (pintype "passive"))
    )
    (net (code "95") (name "unconnected-(U1-14.4-Pad71)") (class "Default")
      (node (ref "U1") (pin "71") (pinfunction "14.4_71") (pintype "passive"))
    )
    (net (code "96") (name "unconnected-(U1-14.5-Pad72)") (class "Default")
      (node (ref "U1") (pin "72") (pinfunction "14.5_72") (pintype "passive"))
    )
    (net (code "97") (name "unconnected-(U1-14.6-Pad73)") (class "Default")
      (node (ref "U1") (pin "73") (pinfunction "14.6_73") (pintype "passive"))
    )
    (net (code "98") (name "unconnected-(U1-15.8-Pad66)") (class "Default")
      (node (ref "U1") (pin "66") (pinfunction "15.8_66") (pintype "passive"))
    )
    (net (code "99") (name "unconnected-(U1-20.0-Pad44)") (class "Default")
      (node (ref "U1") (pin "44") (pinfunction "20.0_44") (pintype "passive"))
    )
    (net (code "100") (name "unconnected-(U1-20.2-Pad45)") (class "Default")
      (node (ref "U1") (pin "45") (pinfunction "20.2_45") (pintype "passive"))
    )
    (net (code "101") (name "unconnected-(U1-20.3-Pad46)") (class "Default")
      (node (ref "U1") (pin "46") (pinfunction "20.3_46") (pintype "passive"))
    )
    (net (code "102") (name "unconnected-(U1-20.6-Pad49)") (class "Default")
      (node (ref "U1") (pin "49") (pinfunction "20.6_49") (pintype "passive"))
    )
    (net (code "103") (name "unconnected-(U1-20.7-Pad50)") (class "Default")
      (node (ref "U1") (pin "50") (pinfunction "20.7_50") (pintype "passive"))
    )
    (net (code "104") (name "unconnected-(U1-20.8-Pad51)") (class "Default")
      (node (ref "U1") (pin "51") (pinfunction "20.8_51") (pintype "passive"))
    )
    (net (code "105") (name "unconnected-(U1-20.10-Pad53)") (class "Default")
      (node (ref "U1") (pin "53") (pinfunction "20.10_53") (pintype "passive"))
    )
    (net (code "106") (name "unconnected-(U1-21.4-Pad40)") (class "Default")
      (node (ref "U1") (pin "40") (pinfunction "21.4_40") (pintype "passive"))
    )
    (net (code "107") (name "unconnected-(U1-21.5-Pad41)") (class "Default")
      (node (ref "U1") (pin "41") (pinfunction "21.5_41") (pintype "passive"))
    )
    (net (code "108") (name "unconnected-(U1-21.6-Pad42)") (class "Default")
      (node (ref "U1") (pin "42") (pinfunction "21.6_42") (pintype "passive"))
    )
    (net (code "109") (name "unconnected-(U1-21.7-Pad43)") (class "Default")
      (node (ref "U1") (pin "43") (pinfunction "21.7_43") (pintype "passive"))
    )
    (net (code "110") (name "unconnected-(U1-22.3-Pad37)") (class "Default")
      (node (ref "U1") (pin "37") (pinfunction "22.3_37") (pintype "passive"))
    )
    (net (code "111") (name "unconnected-(U1-33.4-Pad22)") (class "Default")
      (node (ref "U1") (pin "22") (pinfunction "33.4_22") (pintype "passive"))
    )
    (net (code "112") (name "unconnected-(U1-33.5-Pad23)") (class "Default")
      (node (ref "U1") (pin "23") (pinfunction "33.5_23") (pintype "passive"))
    )
    (net (code "113") (name "unconnected-(U1-33.6-Pad24)") (class "Default")
      (node (ref "U1") (pin "24") (pinfunction "33.6_24") (pintype "passive"))
    )
    (net (code "114") (name "unconnected-(U1-33.7-Pad25)") (class "Default")
      (node (ref "U1") (pin "25") (pinfunction "33.7_25") (pintype "passive"))
    )
    (net (code "115") (name "unconnected-(U1-33.8-Pad26)") (class "Default")
      (node (ref "U1") (pin "26") (pinfunction "33.8_26") (pintype "passive"))
    )
    (net (code "116") (name "unconnected-(U1-33.11-Pad29)") (class "Default")
      (node (ref "U1") (pin "29") (pinfunction "33.11_29") (pintype "passive"))
    )
    (net (code "117") (name "unconnected-(U1-33.12-Pad30)") (class "Default")
      (node (ref "U1") (pin "30") (pinfunction "33.12_30") (pintype "passive"))
    )
    (net (code "118") (name "unconnected-(U1-A0-Pad21)") (class "Default")
      (node (ref "U1") (pin "21") (pinfunction "A0_21") (pintype "passive"))
    )
    (net (code "119") (name "unconnected-(U1-A1-Pad20)") (class "Default")
      (node (ref "U1") (pin "20") (pinfunction "A1_20") (pintype "passive"))
    )
    (net (code "120") (name "unconnected-(U1-A2-Pad19)") (class "Default")
      (node (ref "U1") (pin "19") (pinfunction "A2_19") (pintype "passive"))
    )
    (net (code "121") (name "unconnected-(U1-A3-Pad18)") (class "Default")
      (node (ref "U1") (pin "18") (pinfunction "A3_18") (pintype "passive"))
    )
    (net (code "122") (name "unconnected-(U1-A4-Pad17)") (class "Default")
      (node (ref "U1") (pin "17") (pinfunction "A4_17") (pintype "passive"))
    )
    (net (code "123") (name "unconnected-(U1-A5-Pad16)") (class "Default")
      (node (ref "U1") (pin "16") (pinfunction "A5_16") (pintype "passive"))
    )
    (net (code "124") (name "unconnected-(U1-A6-Pad15)") (class "Default")
      (node (ref "U1") (pin "15") (pinfunction "A6_15") (pintype "passive"))
    )
    (net (code "125") (name "unconnected-(U1-A7-Pad14)") (class "Default")
      (node (ref "U1") (pin "14") (pinfunction "A7_14") (pintype "passive"))
    )
    (net (code "126") (name "unconnected-(U1-A20-Pad6)") (class "Default")
      (node (ref "U1") (pin "6") (pinfunction "A20_6") (pintype "passive"))
    )
    (net (code "127") (name "unconnected-(U1-A21-Pad5)") (class "Default")
      (node (ref "U1") (pin "5") (pinfunction "A21_5") (pintype "passive"))
    )
    (net (code "128") (name "unconnected-(U1-A24-Pad122)") (class "Default")
      (node (ref "U1") (pin "122") (pinfunction "A24_122") (pintype "passive"))
    )
    (net (code "129") (name "unconnected-(U1-A25-Pad121)") (class "Default")
      (node (ref "U1") (pin "121") (pinfunction "A25_121") (pintype "passive"))
    )
    (net (code "130") (name "unconnected-(U1-A35-Pad120)") (class "Default")
      (node (ref "U1") (pin "120") (pinfunction "A35_120") (pintype "passive"))
    )
    (net (code "131") (name "unconnected-(U1-A36-Pad119)") (class "Default")
      (node (ref "U1") (pin "119") (pinfunction "A36_119") (pintype "passive"))
    )
    (net (code "132") (name "unconnected-(U1-A37-Pad118)") (class "Default")
      (node (ref "U1") (pin "118") (pinfunction "A37_118") (pintype "passive"))
    )
    (net (code "133") (name "unconnected-(U1-A38-Pad117)") (class "Default")
      (node (ref "U1") (pin "117") (pinfunction "A38_117") (pintype "passive"))
    )
    (net (code "134") (name "unconnected-(U1-A39-Pad116)") (class "Default")
      (node (ref "U1") (pin "116") (pinfunction "A39_116") (pintype "passive"))
    )
    (net (code "135") (name "unconnected-(U1-A42-Pad115)") (class "Default")
      (node (ref "U1") (pin "115") (pinfunction "A42_115") (pintype "passive"))
    )
    (net (code "136") (name "unconnected-(U1-A43-Pad114)") (class "Default")
      (node (ref "U1") (pin "114") (pinfunction "A43_114") (pintype "passive"))
    )
    (net (code "137") (name "unconnected-(U1-A44-Pad113)") (class "Default")
      (node (ref "U1") (pin "113") (pinfunction "A44_113") (pintype "passive"))
    )
    (net (code "138") (name "unconnected-(U1-A45-Pad112)") (class "Default")
      (node (ref "U1") (pin "112") (pinfunction "A45_112") (pintype "passive"))
    )
    (net (code "139") (name "unconnected-(U1-A46-Pad111)") (class "Default")
      (node (ref "U1") (pin "111") (pinfunction "A46_111") (pintype "passive"))
    )
    (net (code "140") (name "unconnected-(U1-A47-Pad110)") (class "Default")
      (node (ref "U1") (pin "110") (pinfunction "A47_110") (pintype "passive"))
    )
    (net (code "141") (name "unconnected-(U1-ESR0-Pad48)") (class "Default")
      (node (ref "U1") (pin "48") (pinfunction "ESR0_48") (pintype "passive"))
    )
    (net (code "142") (name "unconnected-(U1-ESR1-Pad47)") (class "Default")
      (node (ref "U1") (pin "47") (pinfunction "ESR1_47") (pintype "passive"))
    )
    (net (code "143") (name "unconnected-(U1-GND-Pad1)") (class "Default")
      (node (ref "U1") (pin "1") (pinfunction "GND_1") (pintype "passive"))
    )
    (net (code "144") (name "unconnected-(U1-GND-Pad3)") (class "Default")
      (node (ref "U1") (pin "3") (pinfunction "GND_3") (pintype "passive"))
    )
    (net (code "145") (name "unconnected-(U1-VCC-Pad2)") (class "Default")
      (node (ref "U1") (pin "2") (pinfunction "VCC_2") (pintype "passive"))
    )
    (net (code "146") (name "unconnected-(U1-VCC-Pad4)") (class "Default")
      (node (ref "U1") (pin "4") (pinfunction "VCC_4") (pintype "passive"))
    )
    (net (code "147") (name "unconnected-(U2-NC-Pad4)") (class "Default")
      (node (ref "U2") (pin "4") (pinfunction "NC_4") (pintype "passive+no_connect"))
    )
  )
)
